# 6_RgbLed.net
KiCad netlist of a schematic drawn in Altium Designer
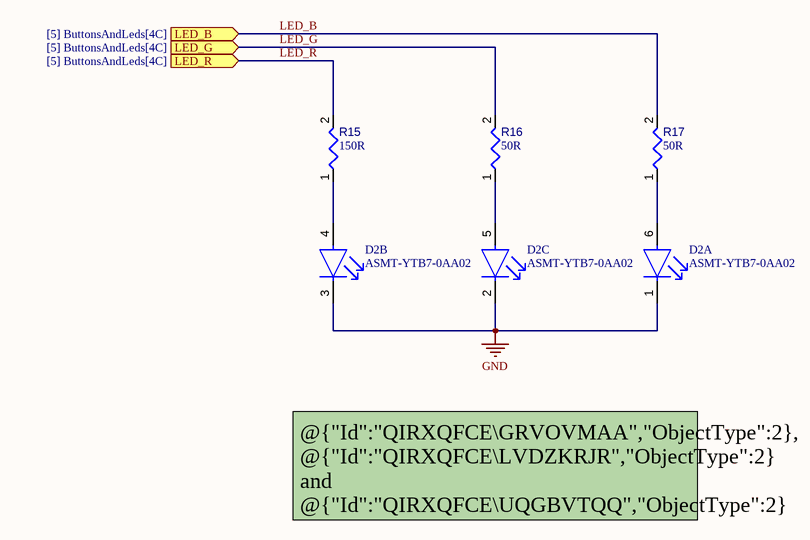
[diagram p0: [6] RgbLed.SchDoc]

(export (version "E")
  (design (tool "Eeschema 10.0.6"))
  (components
    (comp (ref "D2")
      (value "ASMT-YTB7-0AA02")
      (footprint "FP-PLCC-6-MFG")
      (description "LED Tri-Color Blue/Green/Red 469nm/529nm/623nm Chip LED 6-Pin PLCC T/R")
      (libsource (lib "UFCG - Universidade Federal de Campina Grande") (part "0f3d36aaa98356051a15b42400af8f3"))
    )
    (comp (ref "R15")
      (value "150R")
      (footprint "RESC0603(1608)_L")
      (description "SMD Chip Resistor, 150 Ohm, ± 1%, 100 mW, 0603 [1608 Metric], Thick Film, General Purpose")
      (fields (field (name "TOLERANCE") "1%") (field (name "Comment") "CRCW0603150RFKEA"))
      (libsource (lib "UFCG - Universidade Federal de Campina Grande") (part "RES-2"))
    )
    (comp (ref "R16")
      (value "50R")
      (footprint "RESC0603(1608)_L")
      (description "SMD Chip Resistor, 50 Ohm, ± 1%, 100 mW, 0603 [1608 Metric], Thick Film, General Purpose")
      (fields (field (name "TOLERANCE") "1%") (field (name "Comment") "CRCW060350R0FKEA"))
      (libsource (lib "UFCG - Universidade Federal de Campina Grande") (part "RES-2"))
    )
    (comp (ref "R17")
      (value "50R")
      (footprint "RESC0603(1608)_L")
      (description "SMD Chip Resistor, 50 Ohm, ± 1%, 100 mW, 0603 [1608 Metric], Thick Film, General Purpose")
      (fields (field (name "TOLERANCE") "1%") (field (name "Comment") "CRCW060350R0FKEA"))
      (libsource (lib "UFCG - Universidade Federal de Campina Grande") (part "RES-2"))
    )
  )
  (nets
    (net (code "1") (name "/LED_B") (class "Default")
      (node (ref "R17") (pin "2") (pinfunction "2_2") (pintype "passive"))
    )
    (net (code "2") (name "/LED_G") (class "Default")
      (node (ref "R16") (pin "2") (pinfunction "2_2") (pintype "passive"))
    )
    (net (code "3") (name "/LED_R") (class "Default")
      (node (ref "R15") (pin "2") (pinfunction "2_2") (pintype "passive"))
    )
    (net (code "4") (name "GND") (class "Default")
      (node (ref "D2") (pin "1") (pinfunction "Cathode(Blue)_1") (pintype "passive"))
      (node (ref "D2") (pin "2") (pinfunction "Cathode(Green)_2") (pintype "passive"))
      (node (ref "D2") (pin "3") (pinfunction "Cathode(Red)_3") (pintype "passive"))
    )
    (net (code "5") (name "Net-(D2A-Anode(Blue))") (class "Default")
      (node (ref "D2") (pin "6") (pinfunction "Anode(Blue)_6") (pintype "passive"))
      (node (ref "R17") (pin "1") (pinfunction "1_1") (pintype "passive"))
    )
    (net (code "6") (name "Net-(D2B-Anode(Red))") (class "Default")
      (node (ref "D2") (pin "4") (pinfunction "Anode(Red)_4") (pintype "passive"))
      (node (ref "R15") (pin "1") (pinfunction "1_1") (pintype "passive"))
    )
    (net (code "7") (name "Net-(D2C-Anode(Green))") (class "Default")
      (node (ref "D2") (pin "5") (pinfunction "Anode(Green)_5") (pintype "passive"))
      (node (ref "R16") (pin "1") (pinfunction "1_1") (pintype "passive"))
    )
  )
)
